# untitled.net
KiCad netlist of a schematic drawn in EAGLE
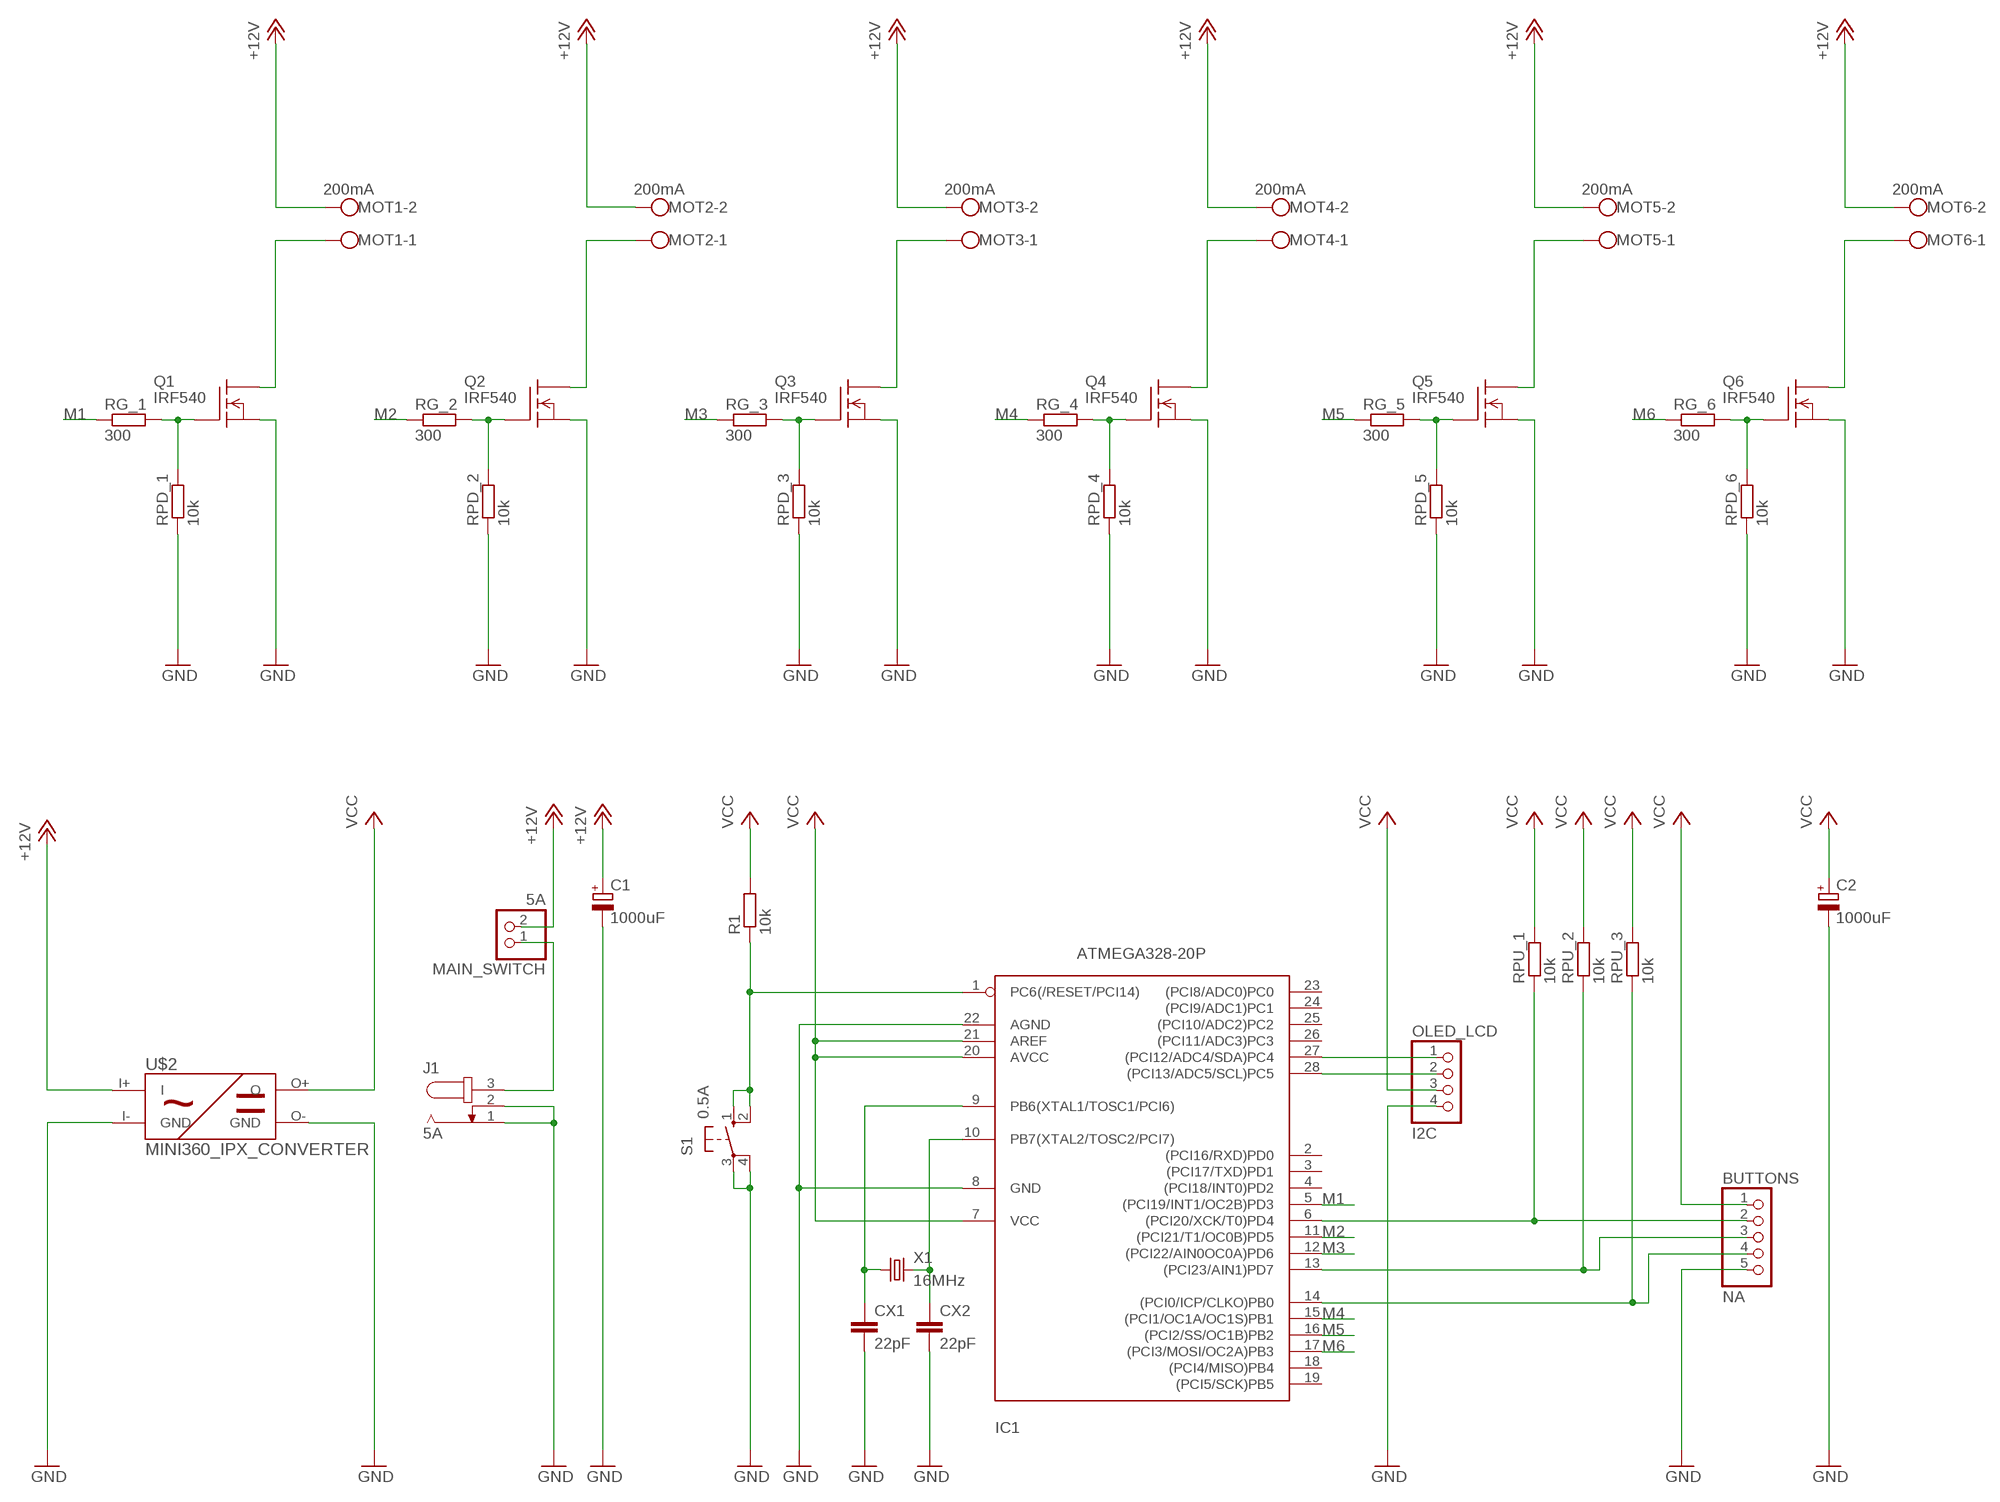
[diagram p0: schematic, sheet 1]

(export (version "E")
  (design (tool "Eeschema 10.0.6"))
  (components
    (comp (ref "BUTTONS")
      (value "NA")
      (footprint "eagle-import:1X05")
      (libsource (lib "eagle-import") (part "PINHD-1X5"))
    )
    (comp (ref "C1")
      (value "1000uF")
      (footprint "eagle-import:E5-8,5")
      (libsource (lib "eagle-import") (part "CPOL-EUE5-8.5"))
    )
    (comp (ref "C2")
      (value "1000uF")
      (footprint "eagle-import:E5-8,5")
      (libsource (lib "eagle-import") (part "CPOL-EUE5-8.5"))
    )
    (comp (ref "CX1")
      (value "22pF")
      (footprint "eagle-import:C025-024X044")
      (libsource (lib "eagle-import") (part "C-EU025-024X044"))
    )
    (comp (ref "CX2")
      (value "22pF")
      (footprint "eagle-import:C025-024X044")
      (libsource (lib "eagle-import") (part "C-EU025-024X044"))
    )
    (comp (ref "IC1")
      (value "ATMEGA328-20P")
      (footprint "eagle-import:DIL28-3")
      (libsource (lib "eagle-import") (part "ATMEGA328P-20"))
    )
    (comp (ref "J1")
      (value "5A")
      (footprint "eagle-import:SPC4078")
      (libsource (lib "eagle-import") (part "JACK-PLUG1"))
    )
    (comp (ref "MAIN_SWITCH")
      (value "5A")
      (footprint "eagle-import:1X02")
      (libsource (lib "eagle-import") (part "PINHD-1X2"))
    )
    (comp (ref "MOT1")
      (value "200mA")
      (footprint "eagle-import:W237-102")
      (fields (field (name "MPN") "237-102"))
      (libsource (lib "eagle-import") (part "W237-102"))
    )
    (comp (ref "MOT2")
      (value "200mA")
      (footprint "eagle-import:W237-102")
      (fields (field (name "MPN") "237-102"))
      (libsource (lib "eagle-import") (part "W237-102"))
    )
    (comp (ref "MOT3")
      (value "200mA")
      (footprint "eagle-import:W237-102")
      (fields (field (name "MPN") "237-102"))
      (libsource (lib "eagle-import") (part "W237-102"))
    )
    (comp (ref "MOT4")
      (value "200mA")
      (footprint "eagle-import:W237-102")
      (fields (field (name "MPN") "237-102"))
      (libsource (lib "eagle-import") (part "W237-102"))
    )
    (comp (ref "MOT5")
      (value "200mA")
      (footprint "eagle-import:W237-102")
      (fields (field (name "MPN") "237-102"))
      (libsource (lib "eagle-import") (part "W237-102"))
    )
    (comp (ref "MOT6")
      (value "200mA")
      (footprint "eagle-import:W237-102")
      (fields (field (name "MPN") "237-102"))
      (libsource (lib "eagle-import") (part "W237-102"))
    )
    (comp (ref "OLED_LCD")
      (value "I2C")
      (footprint "eagle-import:1X04")
      (libsource (lib "eagle-import") (part "PINHD-1X4"))
    )
    (comp (ref "Q1")
      (value "IRF540")
      (footprint "eagle-import:TO220")
      (libsource (lib "eagle-import") (part "IRF540"))
    )
    (comp (ref "Q2")
      (value "IRF540")
      (footprint "eagle-import:TO220")
      (libsource (lib "eagle-import") (part "IRF540"))
    )
    (comp (ref "Q3")
      (value "IRF540")
      (footprint "eagle-import:TO220")
      (libsource (lib "eagle-import") (part "IRF540"))
    )
    (comp (ref "Q4")
      (value "IRF540")
      (footprint "eagle-import:TO220")
      (libsource (lib "eagle-import") (part "IRF540"))
    )
    (comp (ref "Q5")
      (value "IRF540")
      (footprint "eagle-import:TO220")
      (libsource (lib "eagle-import") (part "IRF540"))
    )
    (comp (ref "Q6")
      (value "IRF540")
      (footprint "eagle-import:TO220")
      (libsource (lib "eagle-import") (part "IRF540"))
    )
    (comp (ref "R1")
      (value "10k")
      (footprint "eagle-import:0207_10")
      (libsource (lib "eagle-import") (part "R-EU_0207/10"))
    )
    (comp (ref "RG_1")
      (value "300")
      (footprint "eagle-import:0207_10")
      (libsource (lib "eagle-import") (part "R-EU_0207/10"))
    )
    (comp (ref "RG_2")
      (value "300")
      (footprint "eagle-import:0207_10")
      (libsource (lib "eagle-import") (part "R-EU_0207/10"))
    )
    (comp (ref "RG_3")
      (value "300")
      (footprint "eagle-import:0207_10")
      (libsource (lib "eagle-import") (part "R-EU_0207/10"))
    )
    (comp (ref "RG_4")
      (value "300")
      (footprint "eagle-import:0207_10")
      (libsource (lib "eagle-import") (part "R-EU_0207/10"))
    )
    (comp (ref "RG_5")
      (value "300")
      (footprint "eagle-import:0207_10")
      (libsource (lib "eagle-import") (part "R-EU_0207/10"))
    )
    (comp (ref "RG_6")
      (value "300")
      (footprint "eagle-import:0207_10")
      (libsource (lib "eagle-import") (part "R-EU_0207/10"))
    )
    (comp (ref "RPD_1")
      (value "10k")
      (footprint "eagle-import:0207_10")
      (libsource (lib "eagle-import") (part "R-EU_0207/10"))
    )
    (comp (ref "RPD_2")
      (value "10k")
      (footprint "eagle-import:0207_10")
      (libsource (lib "eagle-import") (part "R-EU_0207/10"))
    )
    (comp (ref "RPD_3")
      (value "10k")
      (footprint "eagle-import:0207_10")
      (libsource (lib "eagle-import") (part "R-EU_0207/10"))
    )
    (comp (ref "RPD_4")
      (value "10k")
      (footprint "eagle-import:0207_10")
      (libsource (lib "eagle-import") (part "R-EU_0207/10"))
    )
    (comp (ref "RPD_5")
      (value "10k")
      (footprint "eagle-import:0207_10")
      (libsource (lib "eagle-import") (part "R-EU_0207/10"))
    )
    (comp (ref "RPD_6")
      (value "10k")
      (footprint "eagle-import:0207_10")
      (libsource (lib "eagle-import") (part "R-EU_0207/10"))
    )
    (comp (ref "RPU_1")
      (value "10k")
      (footprint "eagle-import:0207_10")
      (libsource (lib "eagle-import") (part "R-EU_0207/10"))
    )
    (comp (ref "RPU_2")
      (value "10k")
      (footprint "eagle-import:0207_10")
      (libsource (lib "eagle-import") (part "R-EU_0207/10"))
    )
    (comp (ref "RPU_3")
      (value "10k")
      (footprint "eagle-import:0207_10")
      (libsource (lib "eagle-import") (part "R-EU_0207/10"))
    )
    (comp (ref "S1")
      (value "0.5A")
      (footprint "eagle-import:B3F-10XX")
      (fields (field (name "MPN") "B3F-1000"))
      (libsource (lib "eagle-import") (part "10-XX"))
    )
    (comp (ref "U$2")
      (value "MINI360_IPX_CONVERTER")
      (footprint "eagle-import:MINI360_IPX_CONVERTER")
      (libsource (lib "eagle-import") (part "MINI360_IPX_CONVERTER"))
    )
    (comp (ref "X1")
      (value "16MHz")
      (footprint "eagle-import:HC49_S")
      (libsource (lib "eagle-import") (part "CRYSTALHC49S"))
    )
  )
  (nets
    (net (code "1") (name "+12V") (class "Default")
      (node (ref "C1") (pin "+") (pinfunction "+_+") (pintype "passive"))
      (node (ref "MAIN_SWITCH") (pin "2") (pinfunction "2_2") (pintype "passive"))
      (node (ref "MOT1") (pin "2") (pinfunction "KL_2") (pintype "passive"))
      (node (ref "MOT2") (pin "2") (pinfunction "KL_2") (pintype "passive"))
      (node (ref "MOT3") (pin "2") (pinfunction "KL_2") (pintype "passive"))
      (node (ref "MOT4") (pin "2") (pinfunction "KL_2") (pintype "passive"))
      (node (ref "MOT5") (pin "2") (pinfunction "KL_2") (pintype "passive"))
      (node (ref "MOT6") (pin "2") (pinfunction "KL_2") (pintype "passive"))
      (node (ref "U$2") (pin "I+") (pinfunction "I_I+") (pintype "bidirectional"))
    )
    (net (code "2") (name "/M1") (class "Default")
      (node (ref "IC1") (pin "5") (pinfunction "(PCI19/INT1/OC2B)PD3_5") (pintype "bidirectional"))
      (node (ref "RG_1") (pin "1") (pinfunction "1_1") (pintype "passive"))
    )
    (net (code "3") (name "/M2") (class "Default")
      (node (ref "IC1") (pin "11") (pinfunction "(PCI21/T1/OC0B)PD5_11") (pintype "bidirectional"))
      (node (ref "RG_2") (pin "1") (pinfunction "1_1") (pintype "passive"))
    )
    (net (code "4") (name "/M3") (class "Default")
      (node (ref "IC1") (pin "12") (pinfunction "(PCI22/AIN0OC0A)PD6_12") (pintype "bidirectional"))
      (node (ref "RG_3") (pin "1") (pinfunction "1_1") (pintype "passive"))
    )
    (net (code "5") (name "/M4") (class "Default")
      (node (ref "IC1") (pin "15") (pinfunction "(PCI1/OC1A/OC1S)PB1_15") (pintype "bidirectional"))
      (node (ref "RG_4") (pin "1") (pinfunction "1_1") (pintype "passive"))
    )
    (net (code "6") (name "/M5") (class "Default")
      (node (ref "IC1") (pin "16") (pinfunction "(PCI2/SS/OC1B)PB2_16") (pintype "bidirectional"))
      (node (ref "RG_5") (pin "1") (pinfunction "1_1") (pintype "passive"))
    )
    (net (code "7") (name "/M6") (class "Default")
      (node (ref "IC1") (pin "17") (pinfunction "(PCI3/MOSI/OC2A)PB3_17") (pintype "bidirectional"))
      (node (ref "RG_6") (pin "1") (pinfunction "1_1") (pintype "passive"))
    )
    (net (code "8") (name "GND") (class "Default")
      (node (ref "BUTTONS") (pin "5") (pinfunction "5_5") (pintype "passive"))
      (node (ref "C1") (pin "-") (pinfunction "-_-") (pintype "passive"))
      (node (ref "C2") (pin "-") (pinfunction "-_-") (pintype "passive"))
      (node (ref "CX1") (pin "2") (pinfunction "2_2") (pintype "passive"))
      (node (ref "CX2") (pin "2") (pinfunction "2_2") (pintype "passive"))
      (node (ref "IC1") (pin "22") (pinfunction "AGND_22") (pintype "bidirectional"))
      (node (ref "IC1") (pin "8") (pinfunction "GND_8") (pintype "bidirectional"))
      (node (ref "J1") (pin "1") (pinfunction "1_1") (pintype "passive"))
      (node (ref "J1") (pin "2") (pinfunction "2_2") (pintype "passive"))
      (node (ref "OLED_LCD") (pin "4") (pinfunction "4_4") (pintype "passive"))
      (node (ref "Q1") (pin "3") (pinfunction "S_3") (pintype "passive"))
      (node (ref "Q2") (pin "3") (pinfunction "S_3") (pintype "passive"))
      (node (ref "Q3") (pin "3") (pinfunction "S_3") (pintype "passive"))
      (node (ref "Q4") (pin "3") (pinfunction "S_3") (pintype "passive"))
      (node (ref "Q5") (pin "3") (pinfunction "S_3") (pintype "passive"))
      (node (ref "Q6") (pin "3") (pinfunction "S_3") (pintype "passive"))
      (node (ref "RPD_1") (pin "1") (pinfunction "1_1") (pintype "passive"))
      (node (ref "RPD_2") (pin "1") (pinfunction "1_1") (pintype "passive"))
      (node (ref "RPD_3") (pin "1") (pinfunction "1_1") (pintype "passive"))
      (node (ref "RPD_4") (pin "1") (pinfunction "1_1") (pintype "passive"))
      (node (ref "RPD_5") (pin "1") (pinfunction "1_1") (pintype "passive"))
      (node (ref "RPD_6") (pin "1") (pinfunction "1_1") (pintype "passive"))
      (node (ref "S1") (pin "3") (pinfunction "P_3") (pintype "passive"))
      (node (ref "S1") (pin "4") (pinfunction "P1_4") (pintype "passive"))
      (node (ref "U$2") (pin "I-") (pinfunction "GND_I-") (pintype "bidirectional"))
      (node (ref "U$2") (pin "O-") (pinfunction "GND_O-") (pintype "bidirectional"))
    )
    (net (code "9") (name "Net-(IC1-(PCI0{slash}ICP{slash}CLKO)PB0)") (class "Default")
      (node (ref "BUTTONS") (pin "4") (pinfunction "4_4") (pintype "passive"))
      (node (ref "IC1") (pin "14") (pinfunction "(PCI0/ICP/CLKO)PB0_14") (pintype "bidirectional"))
      (node (ref "RPU_3") (pin "1") (pinfunction "1_1") (pintype "passive"))
    )
    (net (code "10") (name "Net-(IC1-(PCI12{slash}ADC4{slash}SDA)PC4)") (class "Default")
      (node (ref "IC1") (pin "27") (pinfunction "(PCI12/ADC4/SDA)PC4_27") (pintype "bidirectional"))
      (node (ref "OLED_LCD") (pin "1") (pinfunction "1_1") (pintype "passive"))
    )
    (net (code "11") (name "Net-(IC1-(PCI13{slash}ADC5{slash}SCL)PC5)") (class "Default")
      (node (ref "IC1") (pin "28") (pinfunction "(PCI13/ADC5/SCL)PC5_28") (pintype "bidirectional"))
      (node (ref "OLED_LCD") (pin "2") (pinfunction "2_2") (pintype "passive"))
    )
    (net (code "12") (name "Net-(IC1-(PCI20{slash}XCK{slash}T0)PD4)") (class "Default")
      (node (ref "BUTTONS") (pin "2") (pinfunction "2_2") (pintype "passive"))
      (node (ref "IC1") (pin "6") (pinfunction "(PCI20/XCK/T0)PD4_6") (pintype "bidirectional"))
      (node (ref "RPU_1") (pin "1") (pinfunction "1_1") (pintype "passive"))
    )
    (net (code "13") (name "Net-(IC1-(PCI23{slash}AIN1)PD7)") (class "Default")
      (node (ref "BUTTONS") (pin "3") (pinfunction "3_3") (pintype "passive"))
      (node (ref "IC1") (pin "13") (pinfunction "(PCI23/AIN1)PD7_13") (pintype "bidirectional"))
      (node (ref "RPU_2") (pin "1") (pinfunction "1_1") (pintype "passive"))
    )
    (net (code "14") (name "Net-(IC1-PB6(XTAL1{slash}TOSC1{slash}PCI6))") (class "Default")
      (node (ref "CX1") (pin "1") (pinfunction "1_1") (pintype "passive"))
      (node (ref "IC1") (pin "9") (pinfunction "PB6(XTAL1/TOSC1/PCI6)_9") (pintype "bidirectional"))
      (node (ref "X1") (pin "1") (pinfunction "1_1") (pintype "passive"))
    )
    (net (code "15") (name "Net-(IC1-PB7(XTAL2{slash}TOSC2{slash}PCI7))") (class "Default")
      (node (ref "CX2") (pin "1") (pinfunction "1_1") (pintype "passive"))
      (node (ref "IC1") (pin "10") (pinfunction "PB7(XTAL2/TOSC2/PCI7)_10") (pintype "bidirectional"))
      (node (ref "X1") (pin "2") (pinfunction "2_2") (pintype "passive"))
    )
    (net (code "16") (name "Net-(IC1-PC6({slash}RESET{slash}PCI14))") (class "Default")
      (node (ref "IC1") (pin "1") (pinfunction "PC6(/RESET/PCI14)_1") (pintype "bidirectional"))
      (node (ref "R1") (pin "1") (pinfunction "1_1") (pintype "passive"))
      (node (ref "S1") (pin "1") (pinfunction "S_1") (pintype "passive"))
      (node (ref "S1") (pin "2") (pinfunction "S1_2") (pintype "passive"))
    )
    (net (code "17") (name "Net-(J1-Pad3)") (class "Default")
      (node (ref "J1") (pin "3") (pinfunction "3_3") (pintype "passive"))
      (node (ref "MAIN_SWITCH") (pin "1") (pinfunction "1_1") (pintype "passive"))
    )
    (net (code "18") (name "Net-(MOT1A-KL)") (class "Default")
      (node (ref "MOT1") (pin "1") (pinfunction "KL_1") (pintype "passive"))
      (node (ref "Q1") (pin "2") (pinfunction "D_2") (pintype "passive"))
    )
    (net (code "19") (name "Net-(MOT2A-KL)") (class "Default")
      (node (ref "MOT2") (pin "1") (pinfunction "KL_1") (pintype "passive"))
      (node (ref "Q2") (pin "2") (pinfunction "D_2") (pintype "passive"))
    )
    (net (code "20") (name "Net-(MOT3A-KL)") (class "Default")
      (node (ref "MOT3") (pin "1") (pinfunction "KL_1") (pintype "passive"))
      (node (ref "Q3") (pin "2") (pinfunction "D_2") (pintype "passive"))
    )
    (net (code "21") (name "Net-(MOT4A-KL)") (class "Default")
      (node (ref "MOT4") (pin "1") (pinfunction "KL_1") (pintype "passive"))
      (node (ref "Q4") (pin "2") (pinfunction "D_2") (pintype "passive"))
    )
    (net (code "22") (name "Net-(MOT5A-KL)") (class "Default")
      (node (ref "MOT5") (pin "1") (pinfunction "KL_1") (pintype "passive"))
      (node (ref "Q5") (pin "2") (pinfunction "D_2") (pintype "passive"))
    )
    (net (code "23") (name "Net-(MOT6A-KL)") (class "Default")
      (node (ref "MOT6") (pin "1") (pinfunction "KL_1") (pintype "passive"))
      (node (ref "Q6") (pin "2") (pinfunction "D_2") (pintype "passive"))
    )
    (net (code "24") (name "Net-(Q1-G)") (class "Default")
      (node (ref "Q1") (pin "1") (pinfunction "G_1") (pintype "passive"))
      (node (ref "RG_1") (pin "2") (pinfunction "2_2") (pintype "passive"))
      (node (ref "RPD_1") (pin "2") (pinfunction "2_2") (pintype "passive"))
    )
    (net (code "25") (name "Net-(Q2-G)") (class "Default")
      (node (ref "Q2") (pin "1") (pinfunction "G_1") (pintype "passive"))
      (node (ref "RG_2") (pin "2") (pinfunction "2_2") (pintype "passive"))
      (node (ref "RPD_2") (pin "2") (pinfunction "2_2") (pintype "passive"))
    )
    (net (code "26") (name "Net-(Q3-G)") (class "Default")
      (node (ref "Q3") (pin "1") (pinfunction "G_1") (pintype "passive"))
      (node (ref "RG_3") (pin "2") (pinfunction "2_2") (pintype "passive"))
      (node (ref "RPD_3") (pin "2") (pinfunction "2_2") (pintype "passive"))
    )
    (net (code "27") (name "Net-(Q4-G)") (class "Default")
      (node (ref "Q4") (pin "1") (pinfunction "G_1") (pintype "passive"))
      (node (ref "RG_4") (pin "2") (pinfunction "2_2") (pintype "passive"))
      (node (ref "RPD_4") (pin "2") (pinfunction "2_2") (pintype "passive"))
    )
    (net (code "28") (name "Net-(Q5-G)") (class "Default")
      (node (ref "Q5") (pin "1") (pinfunction "G_1") (pintype "passive"))
      (node (ref "RG_5") (pin "2") (pinfunction "2_2") (pintype "passive"))
      (node (ref "RPD_5") (pin "2") (pinfunction "2_2") (pintype "passive"))
    )
    (net (code "29") (name "Net-(Q6-G)") (class "Default")
      (node (ref "Q6") (pin "1") (pinfunction "G_1") (pintype "passive"))
      (node (ref "RG_6") (pin "2") (pinfunction "2_2") (pintype "passive"))
      (node (ref "RPD_6") (pin "2") (pinfunction "2_2") (pintype "passive"))
    )
    (net (code "30") (name "VCC") (class "Default")
      (node (ref "BUTTONS") (pin "1") (pinfunction "1_1") (pintype "passive"))
      (node (ref "C2") (pin "+") (pinfunction "+_+") (pintype "passive"))
      (node (ref "IC1") (pin "20") (pinfunction "AVCC_20") (pintype "bidirectional"))
      (node (ref "IC1") (pin "21") (pinfunction "AREF_21") (pintype "bidirectional"))
      (node (ref "IC1") (pin "7") (pinfunction "VCC_7") (pintype "bidirectional"))
      (node (ref "OLED_LCD") (pin "3") (pinfunction "3_3") (pintype "passive"))
      (node (ref "R1") (pin "2") (pinfunction "2_2") (pintype "passive"))
      (node (ref "RPU_1") (pin "2") (pinfunction "2_2") (pintype "passive"))
      (node (ref "RPU_2") (pin "2") (pinfunction "2_2") (pintype "passive"))
      (node (ref "RPU_3") (pin "2") (pinfunction "2_2") (pintype "passive"))
      (node (ref "U$2") (pin "O+") (pinfunction "O_O+") (pintype "bidirectional"))
    )
    (net (code "31") (name "unconnected-(IC1-(PCI4{slash}MISO)PB4-Pad18)") (class "Default")
      (node (ref "IC1") (pin "18") (pinfunction "(PCI4/MISO)PB4_18") (pintype "bidirectional"))
    )
    (net (code "32") (name "unconnected-(IC1-(PCI5{slash}SCK)PB5-Pad19)") (class "Default")
      (node (ref "IC1") (pin "19") (pinfunction "(PCI5/SCK)PB5_19") (pintype "bidirectional"))
    )
    (net (code "33") (name "unconnected-(IC1-(PCI8{slash}ADC0)PC0-Pad23)") (class "Default")
      (node (ref "IC1") (pin "23") (pinfunction "(PCI8/ADC0)PC0_23") (pintype "bidirectional"))
    )
    (net (code "34") (name "unconnected-(IC1-(PCI9{slash}ADC1)PC1-Pad24)") (class "Default")
      (node (ref "IC1") (pin "24") (pinfunction "(PCI9/ADC1)PC1_24") (pintype "bidirectional"))
    )
    (net (code "35") (name "unconnected-(IC1-(PCI10{slash}ADC2)PC2-Pad25)") (class "Default")
      (node (ref "IC1") (pin "25") (pinfunction "(PCI10/ADC2)PC2_25") (pintype "bidirectional"))
    )
    (net (code "36") (name "unconnected-(IC1-(PCI11{slash}ADC3)PC3-Pad26)") (class "Default")
      (node (ref "IC1") (pin "26") (pinfunction "(PCI11/ADC3)PC3_26") (pintype "bidirectional"))
    )
    (net (code "37") (name "unconnected-(IC1-(PCI16{slash}RXD)PD0-Pad2)") (class "Default")
      (node (ref "IC1") (pin "2") (pinfunction "(PCI16/RXD)PD0_2") (pintype "bidirectional"))
    )
    (net (code "38") (name "unconnected-(IC1-(PCI17{slash}TXD)PD1-Pad3)") (class "Default")
      (node (ref "IC1") (pin "3") (pinfunction "(PCI17/TXD)PD1_3") (pintype "bidirectional"))
    )
    (net (code "39") (name "unconnected-(IC1-(PCI18{slash}INT0)PD2-Pad4)") (class "Default")
      (node (ref "IC1") (pin "4") (pinfunction "(PCI18/INT0)PD2_4") (pintype "bidirectional"))
    )
  )
)
